# RoverWingPogoTester-V1.net
KiCad netlist of a schematic drawn in EAGLE
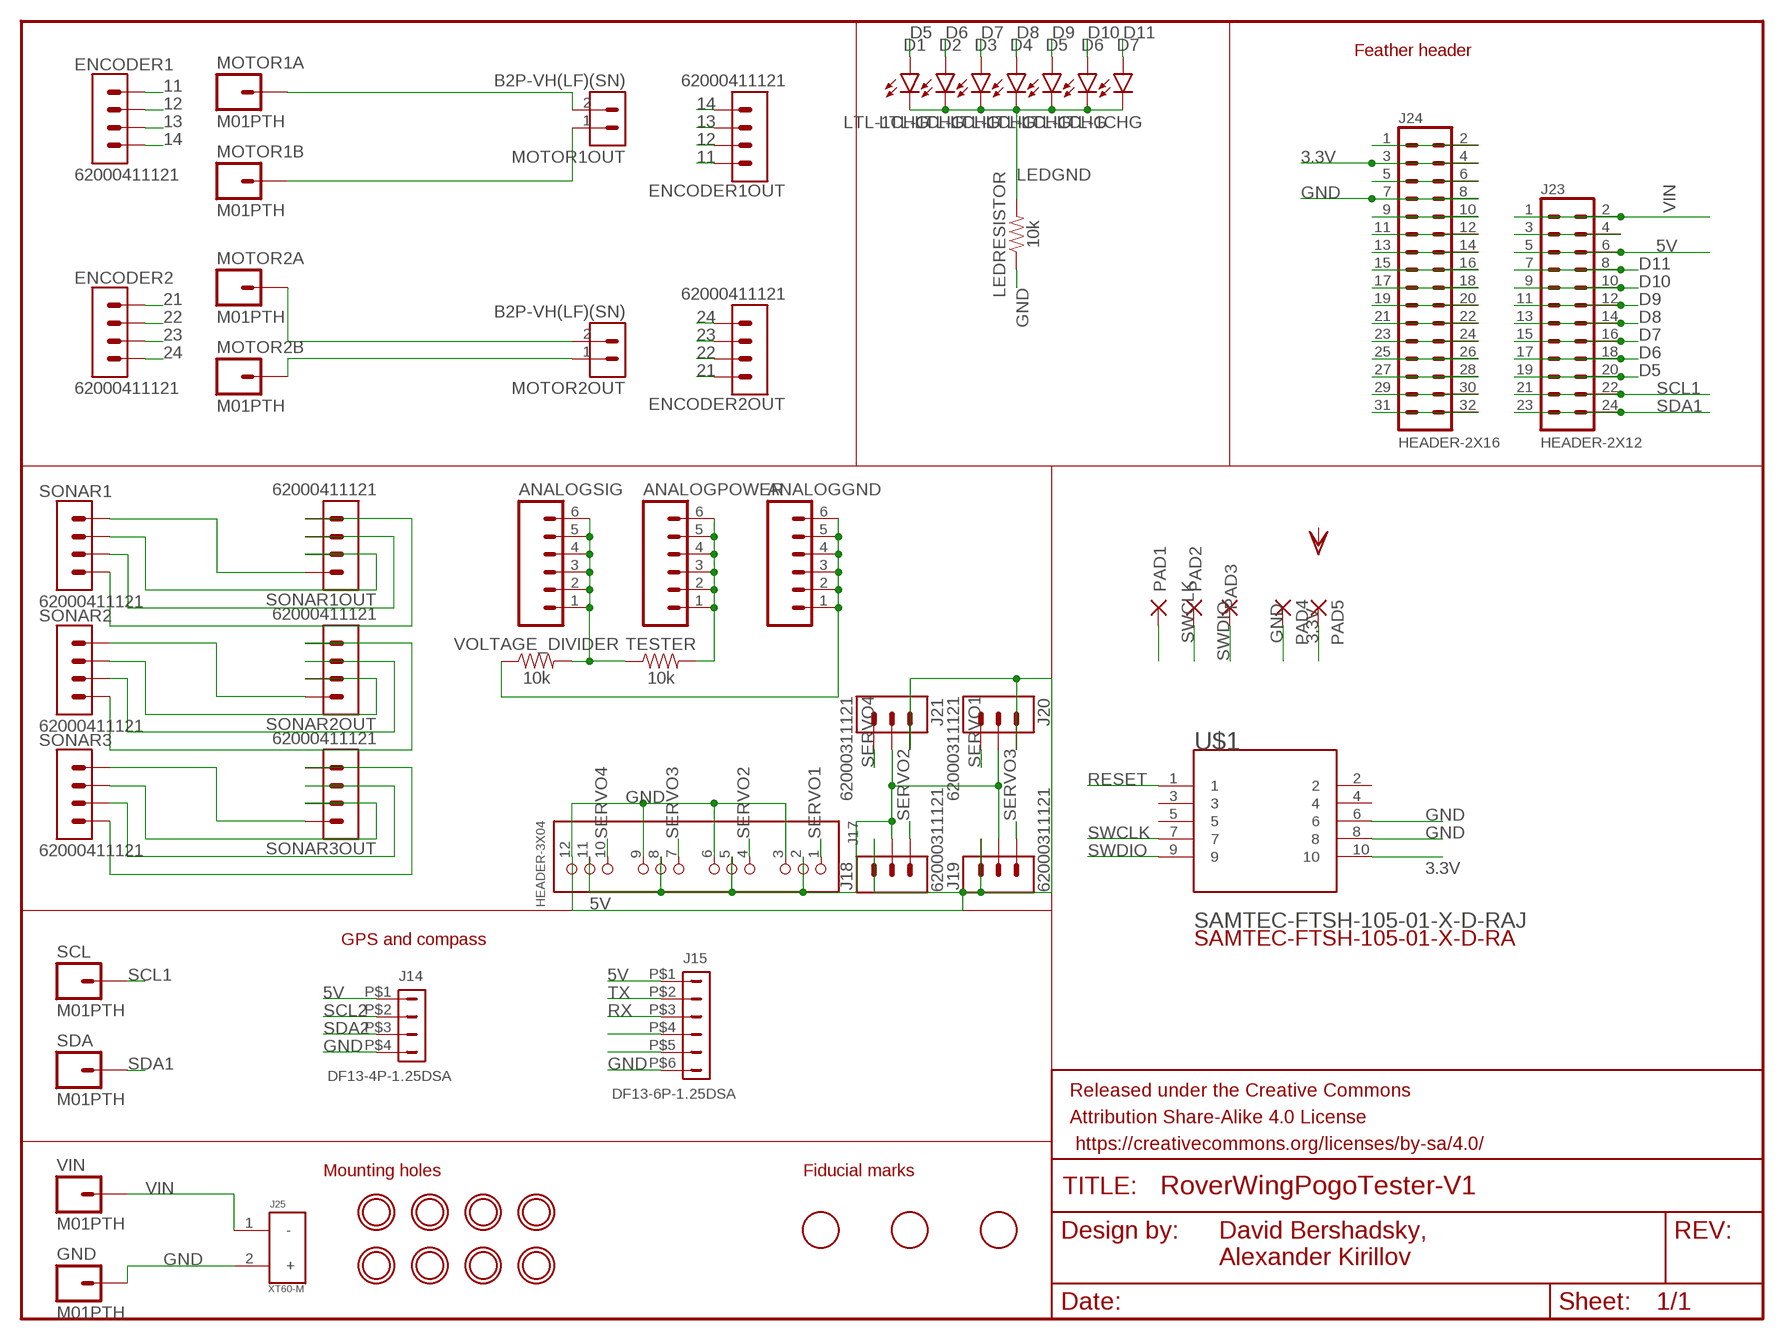
[diagram p0: schematic, sheet 1]

(export (version "E")
  (design (tool "Eeschema 10.0.6"))
  (components
    (comp (ref "ANALOGGND")
      (value "M06SIP")
      (footprint "eagle-import:1X06")
      (libsource (lib "eagle-import") (part "M06SIP"))
    )
    (comp (ref "ANALOGPOWER")
      (value "M06SIP")
      (footprint "eagle-import:1X06")
      (libsource (lib "eagle-import") (part "M06SIP"))
    )
    (comp (ref "ANALOGSIG")
      (value "M06SIP")
      (footprint "eagle-import:1X06")
      (libsource (lib "eagle-import") (part "M06SIP"))
    )
    (comp (ref "D1")
      (value "LTL-1CHG")
      (footprint "eagle-import:RADIAL_3MM")
      (fields
        (field (name "DIGIKEY_PART_NUMBER") "160-1710-ND")
        (field (name "MANUFACTURER") "Lite-On Inc.")
        (field (name "CREATED_BY") "PCBLayout.com")
      )
      (libsource (lib "eagle-import") (part "LTL-1CHG"))
    )
    (comp (ref "D2")
      (value "LTL-1CHG")
      (footprint "eagle-import:RADIAL_3MM")
      (fields
        (field (name "DIGIKEY_PART_NUMBER") "160-1710-ND")
        (field (name "MANUFACTURER") "Lite-On Inc.")
        (field (name "CREATED_BY") "PCBLayout.com")
      )
      (libsource (lib "eagle-import") (part "LTL-1CHG"))
    )
    (comp (ref "D3")
      (value "LTL-1CHG")
      (footprint "eagle-import:RADIAL_3MM")
      (fields
        (field (name "DIGIKEY_PART_NUMBER") "160-1710-ND")
        (field (name "MANUFACTURER") "Lite-On Inc.")
        (field (name "CREATED_BY") "PCBLayout.com")
      )
      (libsource (lib "eagle-import") (part "LTL-1CHG"))
    )
    (comp (ref "D4")
      (value "LTL-1CHG")
      (footprint "eagle-import:RADIAL_3MM")
      (fields
        (field (name "DIGIKEY_PART_NUMBER") "160-1710-ND")
        (field (name "MANUFACTURER") "Lite-On Inc.")
        (field (name "CREATED_BY") "PCBLayout.com")
      )
      (libsource (lib "eagle-import") (part "LTL-1CHG"))
    )
    (comp (ref "D5")
      (value "LTL-1CHG")
      (footprint "eagle-import:RADIAL_3MM")
      (fields
        (field (name "DIGIKEY_PART_NUMBER") "160-1710-ND")
        (field (name "MANUFACTURER") "Lite-On Inc.")
        (field (name "CREATED_BY") "PCBLayout.com")
      )
      (libsource (lib "eagle-import") (part "LTL-1CHG"))
    )
    (comp (ref "D6")
      (value "LTL-1CHG")
      (footprint "eagle-import:RADIAL_3MM")
      (fields
        (field (name "DIGIKEY_PART_NUMBER") "160-1710-ND")
        (field (name "MANUFACTURER") "Lite-On Inc.")
        (field (name "CREATED_BY") "PCBLayout.com")
      )
      (libsource (lib "eagle-import") (part "LTL-1CHG"))
    )
    (comp (ref "D7")
      (value "LTL-1CHG")
      (footprint "eagle-import:RADIAL_3MM")
      (fields
        (field (name "DIGIKEY_PART_NUMBER") "160-1710-ND")
        (field (name "MANUFACTURER") "Lite-On Inc.")
        (field (name "CREATED_BY") "PCBLayout.com")
      )
      (libsource (lib "eagle-import") (part "LTL-1CHG"))
    )
    (comp (ref "ENCODER1")
      (value "62000411121")
      (footprint "eagle-import:62000411121")
      (fields (field (name "MANUFACTURER") "Würth Elektronik ") (field (name "CREATED_BY") "PCBLayout.com"))
      (libsource (lib "eagle-import") (part "62000411121"))
    )
    (comp (ref "ENCODER1OUT")
      (value "62000411121")
      (footprint "eagle-import:62000411121")
      (fields (field (name "MANUFACTURER") "Würth Elektronik ") (field (name "CREATED_BY") "PCBLayout.com"))
      (libsource (lib "eagle-import") (part "62000411121"))
    )
    (comp (ref "ENCODER2")
      (value "62000411121")
      (footprint "eagle-import:62000411121")
      (fields (field (name "MANUFACTURER") "Würth Elektronik ") (field (name "CREATED_BY") "PCBLayout.com"))
      (libsource (lib "eagle-import") (part "62000411121"))
    )
    (comp (ref "ENCODER2OUT")
      (value "62000411121")
      (footprint "eagle-import:62000411121")
      (fields (field (name "MANUFACTURER") "Würth Elektronik ") (field (name "CREATED_BY") "PCBLayout.com"))
      (libsource (lib "eagle-import") (part "62000411121"))
    )
    (comp (ref "FRAME3")
      (value "FRAME-LETTERNO_PACKAGE")
      (footprint "eagle-import:DUMMY")
      (libsource (lib "eagle-import") (part "FRAME-LETTERNO_PACKAGE"))
    )
    (comp (ref "GND")
      (value "M01PTH")
      (footprint "eagle-import:1X01")
      (libsource (lib "eagle-import") (part "M01PTH"))
    )
    (comp (ref "J14")
      (value "DF13-4P-1.25DSA")
      (footprint "eagle-import:DF13-4P-1.25DSA")
      (fields (field (name "MANUFACTURER") "Hirose"))
      (libsource (lib "eagle-import") (part "DF13-4P-1.25DSA"))
    )
    (comp (ref "J15")
      (value "DF13-6P-1.25DSA")
      (footprint "eagle-import:DF13-6P-1.25DSA")
      (fields (field (name "MANUFACTURER") "Hirose"))
      (libsource (lib "eagle-import") (part "DF13-6P-1.25DSA"))
    )
    (comp (ref "J17")
      (value "HEADER-3X04")
      (footprint "eagle-import:3X04")
      (libsource (lib "eagle-import") (part "HEADER-3X04"))
    )
    (comp (ref "J18")
      (value "62000311121")
      (footprint "eagle-import:62000311121")
      (fields (field (name "MANUFACTURER") " Würth Elektronik ") (field (name "CREATED_BY") "PCBLayout.com"))
      (libsource (lib "eagle-import") (part "62000311121"))
    )
    (comp (ref "J19")
      (value "62000311121")
      (footprint "eagle-import:62000311121")
      (fields (field (name "MANUFACTURER") " Würth Elektronik ") (field (name "CREATED_BY") "PCBLayout.com"))
      (libsource (lib "eagle-import") (part "62000311121"))
    )
    (comp (ref "J20")
      (value "62000311121")
      (footprint "eagle-import:62000311121")
      (fields (field (name "MANUFACTURER") " Würth Elektronik ") (field (name "CREATED_BY") "PCBLayout.com"))
      (libsource (lib "eagle-import") (part "62000311121"))
    )
    (comp (ref "J21")
      (value "62000311121")
      (footprint "eagle-import:62000311121")
      (fields (field (name "MANUFACTURER") " Würth Elektronik ") (field (name "CREATED_BY") "PCBLayout.com"))
      (libsource (lib "eagle-import") (part "62000311121"))
    )
    (comp (ref "J23")
      (value "HEADER-2X12")
      (footprint "eagle-import:2X12")
      (fields (field (name "MANUFACTURER") "CONNFLY Elec ") (field (name "PARTNO") "DS1023-2*12SF11 "))
      (libsource (lib "eagle-import") (part "HEADER-2X12"))
    )
    (comp (ref "J24")
      (value "HEADER-2X16")
      (footprint "eagle-import:2X16")
      (fields (field (name "MANUFACTURER") "CONNFLY Elec ") (field (name "PARTNO") "DS1023-2*16SF11 "))
      (libsource (lib "eagle-import") (part "HEADER-2X16"))
    )
    (comp (ref "J25")
      (value "XT60-M")
      (footprint "eagle-import:AMASS_XT60-M")
      (fields (field (name "MF") "AMASS"))
      (libsource (lib "eagle-import") (part "XT60-M"))
    )
    (comp (ref "LEDRESISTOR")
      (value "10k")
      (footprint "eagle-import:AXIAL-0.3")
      (libsource (lib "eagle-import") (part "10KOHM-HORIZ-1/4W-1%"))
    )
    (comp (ref "MOTOR1A")
      (value "M01PTH")
      (footprint "eagle-import:1X01")
      (libsource (lib "eagle-import") (part "M01PTH"))
    )
    (comp (ref "MOTOR1B")
      (value "M01PTH")
      (footprint "eagle-import:1X01")
      (libsource (lib "eagle-import") (part "M01PTH"))
    )
    (comp (ref "MOTOR1OUT")
      (value "B2P-VH(LF)(SN)")
      (footprint "eagle-import:HDR-02")
      (fields
        (field (name "DIGIKEY_PART_NUMBER") "455-1639-ND")
        (field (name "MANUFACTURER") "JST Sales America Inc.")
        (field (name "CREATED_BY") "PCBLayout.com")
      )
      (libsource (lib "eagle-import") (part "B2P-VH(LF)(SN)"))
    )
    (comp (ref "MOTOR2A")
      (value "M01PTH")
      (footprint "eagle-import:1X01")
      (libsource (lib "eagle-import") (part "M01PTH"))
    )
    (comp (ref "MOTOR2B")
      (value "M01PTH")
      (footprint "eagle-import:1X01")
      (libsource (lib "eagle-import") (part "M01PTH"))
    )
    (comp (ref "MOTOR2OUT")
      (value "B2P-VH(LF)(SN)")
      (footprint "eagle-import:HDR-02")
      (fields
        (field (name "DIGIKEY_PART_NUMBER") "455-1639-ND")
        (field (name "MANUFACTURER") "JST Sales America Inc.")
        (field (name "CREATED_BY") "PCBLayout.com")
      )
      (libsource (lib "eagle-import") (part "B2P-VH(LF)(SN)"))
    )
    (comp (ref "PAD1")
      (value "2,15/1,0")
      (footprint "eagle-import:2,15_1,0")
      (libsource (lib "eagle-import") (part "2,15/1,0"))
    )
    (comp (ref "PAD2")
      (value "2,15/1,0")
      (footprint "eagle-import:2,15_1,0")
      (libsource (lib "eagle-import") (part "2,15/1,0"))
    )
    (comp (ref "PAD3")
      (value "2,15/1,0")
      (footprint "eagle-import:2,15_1,0")
      (libsource (lib "eagle-import") (part "2,15/1,0"))
    )
    (comp (ref "PAD4")
      (value "2,15/1,0")
      (footprint "eagle-import:2,15_1,0")
      (libsource (lib "eagle-import") (part "2,15/1,0"))
    )
    (comp (ref "PAD5")
      (value "2,15/1,0")
      (footprint "eagle-import:2,15_1,0")
      (libsource (lib "eagle-import") (part "2,15/1,0"))
    )
    (comp (ref "SCL")
      (value "M01PTH")
      (footprint "eagle-import:1X01")
      (libsource (lib "eagle-import") (part "M01PTH"))
    )
    (comp (ref "SDA")
      (value "M01PTH")
      (footprint "eagle-import:1X01")
      (libsource (lib "eagle-import") (part "M01PTH"))
    )
    (comp (ref "SONAR1")
      (value "62000411121")
      (footprint "eagle-import:62000411121")
      (fields (field (name "MANUFACTURER") "Würth Elektronik ") (field (name "CREATED_BY") "PCBLayout.com"))
      (libsource (lib "eagle-import") (part "62000411121"))
    )
    (comp (ref "SONAR1OUT")
      (value "62000411121")
      (footprint "eagle-import:62000411121")
      (fields (field (name "MANUFACTURER") "Würth Elektronik ") (field (name "CREATED_BY") "PCBLayout.com"))
      (libsource (lib "eagle-import") (part "62000411121"))
    )
    (comp (ref "SONAR2")
      (value "62000411121")
      (footprint "eagle-import:62000411121")
      (fields (field (name "MANUFACTURER") "Würth Elektronik ") (field (name "CREATED_BY") "PCBLayout.com"))
      (libsource (lib "eagle-import") (part "62000411121"))
    )
    (comp (ref "SONAR2OUT")
      (value "62000411121")
      (footprint "eagle-import:62000411121")
      (fields (field (name "MANUFACTURER") "Würth Elektronik ") (field (name "CREATED_BY") "PCBLayout.com"))
      (libsource (lib "eagle-import") (part "62000411121"))
    )
    (comp (ref "SONAR3")
      (value "62000411121")
      (footprint "eagle-import:62000411121")
      (fields (field (name "MANUFACTURER") "Würth Elektronik ") (field (name "CREATED_BY") "PCBLayout.com"))
      (libsource (lib "eagle-import") (part "62000411121"))
    )
    (comp (ref "SONAR3OUT")
      (value "62000411121")
      (footprint "eagle-import:62000411121")
      (fields (field (name "MANUFACTURER") "Würth Elektronik ") (field (name "CREATED_BY") "PCBLayout.com"))
      (libsource (lib "eagle-import") (part "62000411121"))
    )
    (comp (ref "TESTER")
      (value "10k")
      (footprint "eagle-import:AXIAL-0.3")
      (libsource (lib "eagle-import") (part "10KOHM-HORIZ-1/4W-1%"))
    )
    (comp (ref "U$1")
      (value "SAMTEC-FTSH-105-01-X-D-RAJ")
      (footprint "eagle-import:SAMTEC-FTSH-105-01-X-D-RA")
      (fields
        (field (name "DIGI-KEY_PART_NUMBER") "SAM9432-ND")
        (field (name "MF") "Samtec Inc.")
        (field (name "MP") "FTSH-105-01-F-D-RA-K")
      )
      (libsource (lib "eagle-import") (part "SAMTEC-FTSH-105-01-X-D-RAJ"))
    )
    (comp (ref "U$3")
      (value "MOUNTINGHOLE3.0_NPH")
      (footprint "eagle-import:MOUNTINGHOLE_3.0_NPH")
      (libsource (lib "eagle-import") (part "MOUNTINGHOLE3.0_NPH"))
    )
    (comp (ref "U$4")
      (value "MOUNTINGHOLE3.0_NPH")
      (footprint "eagle-import:MOUNTINGHOLE_3.0_NPH")
      (libsource (lib "eagle-import") (part "MOUNTINGHOLE3.0_NPH"))
    )
    (comp (ref "U$11")
      (value "FIDUCIAL")
      (footprint "eagle-import:FIDUCIAL_1MM")
      (libsource (lib "eagle-import") (part "FIDUCIAL"))
    )
    (comp (ref "U$13")
      (value "FIDUCIAL")
      (footprint "eagle-import:FIDUCIAL_1MM")
      (libsource (lib "eagle-import") (part "FIDUCIAL"))
    )
    (comp (ref "U$14")
      (value "MOUNTINGHOLE3.0_NPH")
      (footprint "eagle-import:MOUNTINGHOLE_3.0_NPH")
      (libsource (lib "eagle-import") (part "MOUNTINGHOLE3.0_NPH"))
    )
    (comp (ref "U$15")
      (value "MOUNTINGHOLE3.0_NPH")
      (footprint "eagle-import:MOUNTINGHOLE_3.0_NPH")
      (libsource (lib "eagle-import") (part "MOUNTINGHOLE3.0_NPH"))
    )
    (comp (ref "U$17")
      (value "FIDUCIAL")
      (footprint "eagle-import:FIDUCIAL_1MM")
      (libsource (lib "eagle-import") (part "FIDUCIAL"))
    )
    (comp (ref "U$24")
      (value "MOUNTINGHOLE3.0_NPH")
      (footprint "eagle-import:MOUNTINGHOLE_3.0_NPH")
      (libsource (lib "eagle-import") (part "MOUNTINGHOLE3.0_NPH"))
    )
    (comp (ref "U$25")
      (value "MOUNTINGHOLE3.0_NPH")
      (footprint "eagle-import:MOUNTINGHOLE_3.0_NPH")
      (libsource (lib "eagle-import") (part "MOUNTINGHOLE3.0_NPH"))
    )
    (comp (ref "U$26")
      (value "MOUNTINGHOLE3.0_NPH")
      (footprint "eagle-import:MOUNTINGHOLE_3.0_NPH")
      (libsource (lib "eagle-import") (part "MOUNTINGHOLE3.0_NPH"))
    )
    (comp (ref "U$27")
      (value "MOUNTINGHOLE3.0_NPH")
      (footprint "eagle-import:MOUNTINGHOLE_3.0_NPH")
      (libsource (lib "eagle-import") (part "MOUNTINGHOLE3.0_NPH"))
    )
    (comp (ref "VIN")
      (value "M01PTH")
      (footprint "eagle-import:1X01")
      (libsource (lib "eagle-import") (part "M01PTH"))
    )
    (comp (ref "VOLTAGE_DIVIDER")
      (value "10k")
      (footprint "eagle-import:AXIAL-0.3")
      (libsource (lib "eagle-import") (part "10KOHM-HORIZ-1/4W-1%"))
    )
  )
  (nets
    (net (code "1") (name "/3.3V") (class "Default")
      (node (ref "J24") (pin "3") (pinfunction "3_3") (pintype "passive"))
      (node (ref "J24") (pin "4") (pinfunction "4_4") (pintype "passive"))
      (node (ref "PAD5") (pin "1") (pinfunction "P_1") (pintype "passive"))
      (node (ref "U$1") (pin "10") (pinfunction "10_10") (pintype "passive"))
    )
    (net (code "2") (name "/5V") (class "Default")
      (node (ref "J14") (pin "P$1") (pinfunction "1_P$1") (pintype "passive"))
      (node (ref "J15") (pin "P$1") (pinfunction "1_P$1") (pintype "passive"))
      (node (ref "J17") (pin "11") (pinfunction "11_11") (pintype "passive"))
      (node (ref "J17") (pin "2") (pinfunction "2_2") (pintype "passive"))
      (node (ref "J17") (pin "5") (pinfunction "5_5") (pintype "passive"))
      (node (ref "J17") (pin "8") (pinfunction "8_8") (pintype "passive"))
      (node (ref "J18") (pin "2") (pinfunction "2_2") (pintype "passive"))
      (node (ref "J19") (pin "2") (pinfunction "2_2") (pintype "passive"))
      (node (ref "J20") (pin "2") (pinfunction "2_2") (pintype "passive"))
      (node (ref "J21") (pin "2") (pinfunction "2_2") (pintype "passive"))
      (node (ref "J23") (pin "5") (pinfunction "5_5") (pintype "passive"))
      (node (ref "J23") (pin "6") (pinfunction "6_6") (pintype "passive"))
    )
    (net (code "3") (name "/11") (class "Default")
      (node (ref "ENCODER1") (pin "1") (pinfunction "1_1") (pintype "passive"))
      (node (ref "ENCODER1OUT") (pin "1") (pinfunction "1_1") (pintype "passive"))
    )
    (net (code "4") (name "/12") (class "Default")
      (node (ref "ENCODER1") (pin "2") (pinfunction "2_2") (pintype "passive"))
      (node (ref "ENCODER1OUT") (pin "2") (pinfunction "2_2") (pintype "passive"))
    )
    (net (code "5") (name "/13") (class "Default")
      (node (ref "ENCODER1") (pin "3") (pinfunction "3_3") (pintype "passive"))
      (node (ref "ENCODER1OUT") (pin "3") (pinfunction "3_3") (pintype "passive"))
    )
    (net (code "6") (name "/14") (class "Default")
      (node (ref "ENCODER1") (pin "4") (pinfunction "4_4") (pintype "passive"))
      (node (ref "ENCODER1OUT") (pin "4") (pinfunction "4_4") (pintype "passive"))
    )
    (net (code "7") (name "/21") (class "Default")
      (node (ref "ENCODER2") (pin "1") (pinfunction "1_1") (pintype "passive"))
      (node (ref "ENCODER2OUT") (pin "1") (pinfunction "1_1") (pintype "passive"))
    )
    (net (code "8") (name "/22") (class "Default")
      (node (ref "ENCODER2") (pin "2") (pinfunction "2_2") (pintype "passive"))
      (node (ref "ENCODER2OUT") (pin "2") (pinfunction "2_2") (pintype "passive"))
    )
    (net (code "9") (name "/23") (class "Default")
      (node (ref "ENCODER2") (pin "3") (pinfunction "3_3") (pintype "passive"))
      (node (ref "ENCODER2OUT") (pin "3") (pinfunction "3_3") (pintype "passive"))
    )
    (net (code "10") (name "/24") (class "Default")
      (node (ref "ENCODER2") (pin "4") (pinfunction "4_4") (pintype "passive"))
      (node (ref "ENCODER2OUT") (pin "4") (pinfunction "4_4") (pintype "passive"))
    )
    (net (code "11") (name "/D5") (class "Default")
      (node (ref "D1") (pin "A") (pinfunction "A_A") (pintype "passive"))
      (node (ref "J23") (pin "19") (pinfunction "19_19") (pintype "passive"))
      (node (ref "J23") (pin "20") (pinfunction "20_20") (pintype "passive"))
    )
    (net (code "12") (name "/D6") (class "Default")
      (node (ref "D2") (pin "A") (pinfunction "A_A") (pintype "passive"))
      (node (ref "J23") (pin "17") (pinfunction "17_17") (pintype "passive"))
      (node (ref "J23") (pin "18") (pinfunction "18_18") (pintype "passive"))
    )
    (net (code "13") (name "/D7") (class "Default")
      (node (ref "D3") (pin "A") (pinfunction "A_A") (pintype "passive"))
      (node (ref "J23") (pin "15") (pinfunction "15_15") (pintype "passive"))
      (node (ref "J23") (pin "16") (pinfunction "16_16") (pintype "passive"))
    )
    (net (code "14") (name "/D8") (class "Default")
      (node (ref "D4") (pin "A") (pinfunction "A_A") (pintype "passive"))
      (node (ref "J23") (pin "13") (pinfunction "13_13") (pintype "passive"))
      (node (ref "J23") (pin "14") (pinfunction "14_14") (pintype "passive"))
    )
    (net (code "15") (name "/D9") (class "Default")
      (node (ref "D5") (pin "A") (pinfunction "A_A") (pintype "passive"))
      (node (ref "J23") (pin "11") (pinfunction "11_11") (pintype "passive"))
      (node (ref "J23") (pin "12") (pinfunction "12_12") (pintype "passive"))
    )
    (net (code "16") (name "/D10") (class "Default")
      (node (ref "D6") (pin "A") (pinfunction "A_A") (pintype "passive"))
      (node (ref "J23") (pin "10") (pinfunction "10_10") (pintype "passive"))
      (node (ref "J23") (pin "9") (pinfunction "9_9") (pintype "passive"))
    )
    (net (code "17") (name "/D11") (class "Default")
      (node (ref "D7") (pin "A") (pinfunction "A_A") (pintype "passive"))
      (node (ref "J23") (pin "7") (pinfunction "7_7") (pintype "passive"))
      (node (ref "J23") (pin "8") (pinfunction "8_8") (pintype "passive"))
    )
    (net (code "18") (name "/GND") (class "Default")
      (node (ref "GND") (pin "1") (pinfunction "1_1") (pintype "passive"))
      (node (ref "J14") (pin "P$4") (pinfunction "4_P$4") (pintype "passive"))
      (node (ref "J15") (pin "P$6") (pinfunction "6_P$6") (pintype "passive"))
      (node (ref "J17") (pin "12") (pinfunction "12_12") (pintype "passive"))
      (node (ref "J17") (pin "3") (pinfunction "3_3") (pintype "passive"))
      (node (ref "J17") (pin "6") (pinfunction "6_6") (pintype "passive"))
      (node (ref "J17") (pin "9") (pinfunction "9_9") (pintype "passive"))
      (node (ref "J18") (pin "1") (pinfunction "1_1") (pintype "passive"))
      (node (ref "J19") (pin "1") (pinfunction "1_1") (pintype "passive"))
      (node (ref "J20") (pin "1") (pinfunction "1_1") (pintype "passive"))
      (node (ref "J21") (pin "1") (pinfunction "1_1") (pintype "passive"))
      (node (ref "J24") (pin "7") (pinfunction "7_7") (pintype "passive"))
      (node (ref "J24") (pin "8") (pinfunction "8_8") (pintype "passive"))
      (node (ref "J25") (pin "2") (pinfunction "+_2") (pintype "passive"))
      (node (ref "LEDRESISTOR") (pin "P$1") (pinfunction "1_P$1") (pintype "passive"))
      (node (ref "PAD4") (pin "1") (pinfunction "P_1") (pintype "passive"))
      (node (ref "U$1") (pin "6") (pinfunction "6_6") (pintype "passive"))
      (node (ref "U$1") (pin "8") (pinfunction "8_8") (pintype "passive"))
    )
    (net (code "19") (name "/LEDGND") (class "Default")
      (node (ref "D1") (pin "C") (pinfunction "C_C") (pintype "passive"))
      (node (ref "D2") (pin "C") (pinfunction "C_C") (pintype "passive"))
      (node (ref "D3") (pin "C") (pinfunction "C_C") (pintype "passive"))
      (node (ref "D4") (pin "C") (pinfunction "C_C") (pintype "passive"))
      (node (ref "D5") (pin "C") (pinfunction "C_C") (pintype "passive"))
      (node (ref "D6") (pin "C") (pinfunction "C_C") (pintype "passive"))
      (node (ref "D7") (pin "C") (pinfunction "C_C") (pintype "passive"))
      (node (ref "LEDRESISTOR") (pin "P$2") (pinfunction "2_P$2") (pintype "passive"))
    )
    (net (code "20") (name "/RESET") (class "Default")
      (node (ref "PAD1") (pin "1") (pinfunction "P_1") (pintype "passive"))
      (node (ref "U$1") (pin "1") (pinfunction "1_1") (pintype "passive"))
    )
    (net (code "21") (name "/RX") (class "Default")
      (node (ref "J15") (pin "P$3") (pinfunction "3_P$3") (pintype "passive"))
    )
    (net (code "22") (name "/SCL1") (class "Default")
      (node (ref "J23") (pin "21") (pinfunction "21_21") (pintype "passive"))
      (node (ref "J23") (pin "22") (pinfunction "22_22") (pintype "passive"))
      (node (ref "SCL") (pin "1") (pinfunction "1_1") (pintype "passive"))
    )
    (net (code "23") (name "/SCL2") (class "Default")
      (node (ref "J14") (pin "P$2") (pinfunction "2_P$2") (pintype "passive"))
    )
    (net (code "24") (name "/SDA1") (class "Default")
      (node (ref "J23") (pin "23") (pinfunction "23_23") (pintype "passive"))
      (node (ref "J23") (pin "24") (pinfunction "24_24") (pintype "passive"))
      (node (ref "SDA") (pin "1") (pinfunction "1_1") (pintype "passive"))
    )
    (net (code "25") (name "/SDA2") (class "Default")
      (node (ref "J14") (pin "P$3") (pinfunction "3_P$3") (pintype "passive"))
    )
    (net (code "26") (name "/SERVO1") (class "Default")
      (node (ref "J17") (pin "1") (pinfunction "1_1") (pintype "passive"))
      (node (ref "J20") (pin "3") (pinfunction "3_3") (pintype "passive"))
    )
    (net (code "27") (name "/SERVO2") (class "Default")
      (node (ref "J17") (pin "4") (pinfunction "4_4") (pintype "passive"))
      (node (ref "J18") (pin "3") (pinfunction "3_3") (pintype "passive"))
    )
    (net (code "28") (name "/SERVO3") (class "Default")
      (node (ref "J17") (pin "7") (pinfunction "7_7") (pintype "passive"))
      (node (ref "J19") (pin "3") (pinfunction "3_3") (pintype "passive"))
    )
    (net (code "29") (name "/SERVO4") (class "Default")
      (node (ref "J17") (pin "10") (pinfunction "10_10") (pintype "passive"))
      (node (ref "J21") (pin "3") (pinfunction "3_3") (pintype "passive"))
    )
    (net (code "30") (name "/SWCLK") (class "Default")
      (node (ref "PAD2") (pin "1") (pinfunction "P_1") (pintype "passive"))
      (node (ref "U$1") (pin "7") (pinfunction "7_7") (pintype "passive"))
    )
    (net (code "31") (name "/SWDIO") (class "Default")
      (node (ref "PAD3") (pin "1") (pinfunction "P_1") (pintype "passive"))
      (node (ref "U$1") (pin "9") (pinfunction "9_9") (pintype "passive"))
    )
    (net (code "32") (name "/TX") (class "Default")
      (node (ref "J15") (pin "P$2") (pinfunction "2_P$2") (pintype "passive"))
    )
    (net (code "33") (name "/VIN") (class "Default")
      (node (ref "J23") (pin "1") (pinfunction "1_1") (pintype "passive"))
      (node (ref "J23") (pin "2") (pinfunction "2_2") (pintype "passive"))
      (node (ref "J25") (pin "1") (pinfunction "-_1") (pintype "passive"))
      (node (ref "VIN") (pin "1") (pinfunction "1_1") (pintype "passive"))
    )
    (net (code "34") (name "Net-(J23-Pad3)") (class "Default")
      (node (ref "J23") (pin "3") (pinfunction "3_3") (pintype "passive"))
      (node (ref "J23") (pin "4") (pinfunction "4_4") (pintype "passive"))
    )
    (net (code "35") (name "Net-(J24-Pad1)") (class "Default")
      (node (ref "J24") (pin "1") (pinfunction "1_1") (pintype "passive"))
      (node (ref "J24") (pin "2") (pinfunction "2_2") (pintype "passive"))
    )
    (net (code "36") (name "Net-(J24-Pad5)") (class "Default")
      (node (ref "J24") (pin "5") (pinfunction "5_5") (pintype "passive"))
      (node (ref "J24") (pin "6") (pinfunction "6_6") (pintype "passive"))
    )
    (net (code "37") (name "Net-(J24-Pad10)") (class "Default")
      (node (ref "J24") (pin "10") (pinfunction "10_10") (pintype "passive"))
      (node (ref "J24") (pin "9") (pinfunction "9_9") (pintype "passive"))
    )
    (net (code "38") (name "Net-(J24-Pad11)") (class "Default")
      (node (ref "J24") (pin "11") (pinfunction "11_11") (pintype "passive"))
      (node (ref "J24") (pin "12") (pinfunction "12_12") (pintype "passive"))
    )
    (net (code "39") (name "Net-(J24-Pad13)") (class "Default")
      (node (ref "J24") (pin "13") (pinfunction "13_13") (pintype "passive"))
      (node (ref "J24") (pin "14") (pinfunction "14_14") (pintype "passive"))
    )
    (net (code "40") (name "Net-(J24-Pad15)") (class "Default")
      (node (ref "J24") (pin "15") (pinfunction "15_15") (pintype "passive"))
      (node (ref "J24") (pin "16") (pinfunction "16_16") (pintype "passive"))
    )
    (net (code "41") (name "Net-(J24-Pad17)") (class "Default")
      (node (ref "J24") (pin "17") (pinfunction "17_17") (pintype "passive"))
      (node (ref "J24") (pin "18") (pinfunction "18_18") (pintype "passive"))
    )
    (net (code "42") (name "Net-(J24-Pad19)") (class "Default")
      (node (ref "J24") (pin "19") (pinfunction "19_19") (pintype "passive"))
      (node (ref "J24") (pin "20") (pinfunction "20_20") (pintype "passive"))
    )
    (net (code "43") (name "Net-(J24-Pad21)") (class "Default")
      (node (ref "J24") (pin "21") (pinfunction "21_21") (pintype "passive"))
      (node (ref "J24") (pin "22") (pinfunction "22_22") (pintype "passive"))
    )
    (net (code "44") (name "Net-(J24-Pad23)") (class "Default")
      (node (ref "J24") (pin "23") (pinfunction "23_23") (pintype "passive"))
      (node (ref "J24") (pin "24") (pinfunction "24_24") (pintype "passive"))
    )
    (net (code "45") (name "Net-(J24-Pad25)") (class "Default")
      (node (ref "J24") (pin "25") (pinfunction "25_25") (pintype "passive"))
      (node (ref "J24") (pin "26") (pinfunction "26_26") (pintype "passive"))
    )
    (net (code "46") (name "Net-(J24-Pad27)") (class "Default")
      (node (ref "J24") (pin "27") (pinfunction "27_27") (pintype "passive"))
      (node (ref "J24") (pin "28") (pinfunction "28_28") (pintype "passive"))
    )
    (net (code "47") (name "Net-(J24-Pad29)") (class "Default")
      (node (ref "J24") (pin "29") (pinfunction "29_29") (pintype "passive"))
      (node (ref "J24") (pin "30") (pinfunction "30_30") (pintype "passive"))
    )
    (net (code "48") (name "Net-(J24-Pad31)") (class "Default")
      (node (ref "J24") (pin "31") (pinfunction "31_31") (pintype "passive"))
      (node (ref "J24") (pin "32") (pinfunction "32_32") (pintype "passive"))
    )
    (net (code "49") (name "Net-(MOTOR1A-Pad1)") (class "Default")
      (node (ref "MOTOR1A") (pin "1") (pinfunction "1_1") (pintype "passive"))
      (node (ref "MOTOR1OUT") (pin "2") (pinfunction "2_2") (pintype "passive"))
    )
    (net (code "50") (name "Net-(MOTOR1B-Pad1)") (class "Default")
      (node (ref "MOTOR1B") (pin "1") (pinfunction "1_1") (pintype "passive"))
      (node (ref "MOTOR1OUT") (pin "1") (pinfunction "1_1") (pintype "passive"))
    )
    (net (code "51") (name "Net-(MOTOR2A-Pad1)") (class "Default")
      (node (ref "MOTOR2A") (pin "1") (pinfunction "1_1") (pintype "passive"))
      (node (ref "MOTOR2OUT") (pin "2") (pinfunction "2_2") (pintype "passive"))
    )
    (net (code "52") (name "Net-(MOTOR2B-Pad1)") (class "Default")
      (node (ref "MOTOR2B") (pin "1") (pinfunction "1_1") (pintype "passive"))
      (node (ref "MOTOR2OUT") (pin "1") (pinfunction "1_1") (pintype "passive"))
    )
    (net (code "53") (name "Net-(SONAR1-Pad1)") (class "Default")
      (node (ref "SONAR1") (pin "1") (pinfunction "1_1") (pintype "passive"))
      (node (ref "SONAR1OUT") (pin "1") (pinfunction "1_1") (pintype "passive"))
    )
    (net (code "54") (name "Net-(SONAR1-Pad2)") (class "Default")
      (node (ref "SONAR1") (pin "2") (pinfunction "2_2") (pintype "passive"))
      (node (ref "SONAR1OUT") (pin "2") (pinfunction "2_2") (pintype "passive"))
    )
    (net (code "55") (name "Net-(SONAR1-Pad3)") (class "Default")
      (node (ref "SONAR1") (pin "3") (pinfunction "3_3") (pintype "passive"))
      (node (ref "SONAR1OUT") (pin "3") (pinfunction "3_3") (pintype "passive"))
    )
    (net (code "56") (name "Net-(SONAR1-Pad4)") (class "Default")
      (node (ref "SONAR1") (pin "4") (pinfunction "4_4") (pintype "passive"))
      (node (ref "SONAR1OUT") (pin "4") (pinfunction "4_4") (pintype "passive"))
    )
    (net (code "57") (name "Net-(SONAR2-Pad1)") (class "Default")
      (node (ref "SONAR2") (pin "1") (pinfunction "1_1") (pintype "passive"))
      (node (ref "SONAR2OUT") (pin "1") (pinfunction "1_1") (pintype "passive"))
    )
    (net (code "58") (name "Net-(SONAR2-Pad2)") (class "Default")
      (node (ref "SONAR2") (pin "2") (pinfunction "2_2") (pintype "passive"))
      (node (ref "SONAR2OUT") (pin "2") (pinfunction "2_2") (pintype "passive"))
    )
    (net (code "59") (name "Net-(SONAR2-Pad3)") (class "Default")
      (node (ref "SONAR2") (pin "3") (pinfunction "3_3") (pintype "passive"))
      (node (ref "SONAR2OUT") (pin "3") (pinfunction "3_3") (pintype "passive"))
    )
    (net (code "60") (name "Net-(SONAR2-Pad4)") (class "Default")
      (node (ref "SONAR2") (pin "4") (pinfunction "4_4") (pintype "passive"))
      (node (ref "SONAR2OUT") (pin "4") (pinfunction "4_4") (pintype "passive"))
    )
    (net (code "61") (name "Net-(SONAR3-Pad1)") (class "Default")
      (node (ref "SONAR3") (pin "1") (pinfunction "1_1") (pintype "passive"))
      (node (ref "SONAR3OUT") (pin "1") (pinfunction "1_1") (pintype "passive"))
    )
    (net (code "62") (name "Net-(SONAR3-Pad2)") (class "Default")
      (node (ref "SONAR3") (pin "2") (pinfunction "2_2") (pintype "passive"))
      (node (ref "SONAR3OUT") (pin "2") (pinfunction "2_2") (pintype "passive"))
    )
    (net (code "63") (name "Net-(SONAR3-Pad3)") (class "Default")
      (node (ref "SONAR3") (pin "3") (pinfunction "3_3") (pintype "passive"))
      (node (ref "SONAR3OUT") (pin "3") (pinfunction "3_3") (pintype "passive"))
    )
    (net (code "64") (name "Net-(SONAR3-Pad4)") (class "Default")
      (node (ref "SONAR3") (pin "4") (pinfunction "4_4") (pintype "passive"))
      (node (ref "SONAR3OUT") (pin "4") (pinfunction "4_4") (pintype "passive"))
    )
    (net (code "65") (name "Net-(TESTER-1)") (class "Default")
      (node (ref "ANALOGSIG") (pin "1") (pinfunction "1_1") (pintype "passive"))
      (node (ref "ANALOGSIG") (pin "2") (pinfunction "2_2") (pintype "passive"))
      (node (ref "ANALOGSIG") (pin "3") (pinfunction "3_3") (pintype "passive"))
      (node (ref "ANALOGSIG") (pin "4") (pinfunction "4_4") (pintype "passive"))
      (node (ref "ANALOGSIG") (pin "5") (pinfunction "5_5") (pintype "passive"))
      (node (ref "ANALOGSIG") (pin "6") (pinfunction "6_6") (pintype "passive"))
      (node (ref "TESTER") (pin "P$1") (pinfunction "1_P$1") (pintype "passive"))
      (node (ref "VOLTAGE_DIVIDER") (pin "P$2") (pinfunction "2_P$2") (pintype "passive"))
    )
    (net (code "66") (name "Net-(TESTER-2)") (class "Default")
      (node (ref "ANALOGPOWER") (pin "1") (pinfunction "1_1") (pintype "passive"))
      (node (ref "ANALOGPOWER") (pin "2") (pinfunction "2_2") (pintype "passive"))
      (node (ref "ANALOGPOWER") (pin "3") (pinfunction "3_3") (pintype "passive"))
      (node (ref "ANALOGPOWER") (pin "4") (pinfunction "4_4") (pintype "passive"))
      (node (ref "ANALOGPOWER") (pin "5") (pinfunction "5_5") (pintype "passive"))
      (node (ref "ANALOGPOWER") (pin "6") (pinfunction "6_6") (pintype "passive"))
      (node (ref "TESTER") (pin "P$2") (pinfunction "2_P$2") (pintype "passive"))
    )
    (net (code "67") (name "Net-(VOLTAGE_DIVIDER-1)") (class "Default")
      (node (ref "ANALOGGND") (pin "1") (pinfunction "1_1") (pintype "passive"))
      (node (ref "ANALOGGND") (pin "2") (pinfunction "2_2") (pintype "passive"))
      (node (ref "ANALOGGND") (pin "3") (pinfunction "3_3") (pintype "passive"))
      (node (ref "ANALOGGND") (pin "4") (pinfunction "4_4") (pintype "passive"))
      (node (ref "ANALOGGND") (pin "5") (pinfunction "5_5") (pintype "passive"))
      (node (ref "ANALOGGND") (pin "6") (pinfunction "6_6") (pintype "passive"))
      (node (ref "VOLTAGE_DIVIDER") (pin "P$1") (pinfunction "1_P$1") (pintype "passive"))
    )
    (net (code "69") (name "unconnected-(J15-4-PadP$4)") (class "Default")
      (node (ref "J15") (pin "P$4") (pinfunction "4_P$4") (pintype "passive"))
    )
    (net (code "70") (name "unconnected-(J15-5-PadP$5)") (class "Default")
      (node (ref "J15") (pin "P$5") (pinfunction "5_P$5") (pintype "passive"))
    )
    (net (code "71") (name "unconnected-(U$1-Pad2)") (class "Default")
      (node (ref "U$1") (pin "2") (pinfunction "2_2") (pintype "passive"))
    )
    (net (code "72") (name "unconnected-(U$1-Pad3)") (class "Default")
      (node (ref "U$1") (pin "3") (pinfunction "3_3") (pintype "passive"))
    )
    (net (code "73") (name "unconnected-(U$1-Pad4)") (class "Default")
      (node (ref "U$1") (pin "4") (pinfunction "4_4") (pintype "passive"))
    )
    (net (code "74") (name "unconnected-(U$1-Pad5)") (class "Default")
      (node (ref "U$1") (pin "5") (pinfunction "5_5") (pintype "passive"))
    )
  )
)
